# SensWear_Haptic.net
KiCad netlist of a schematic drawn in Altium Designer
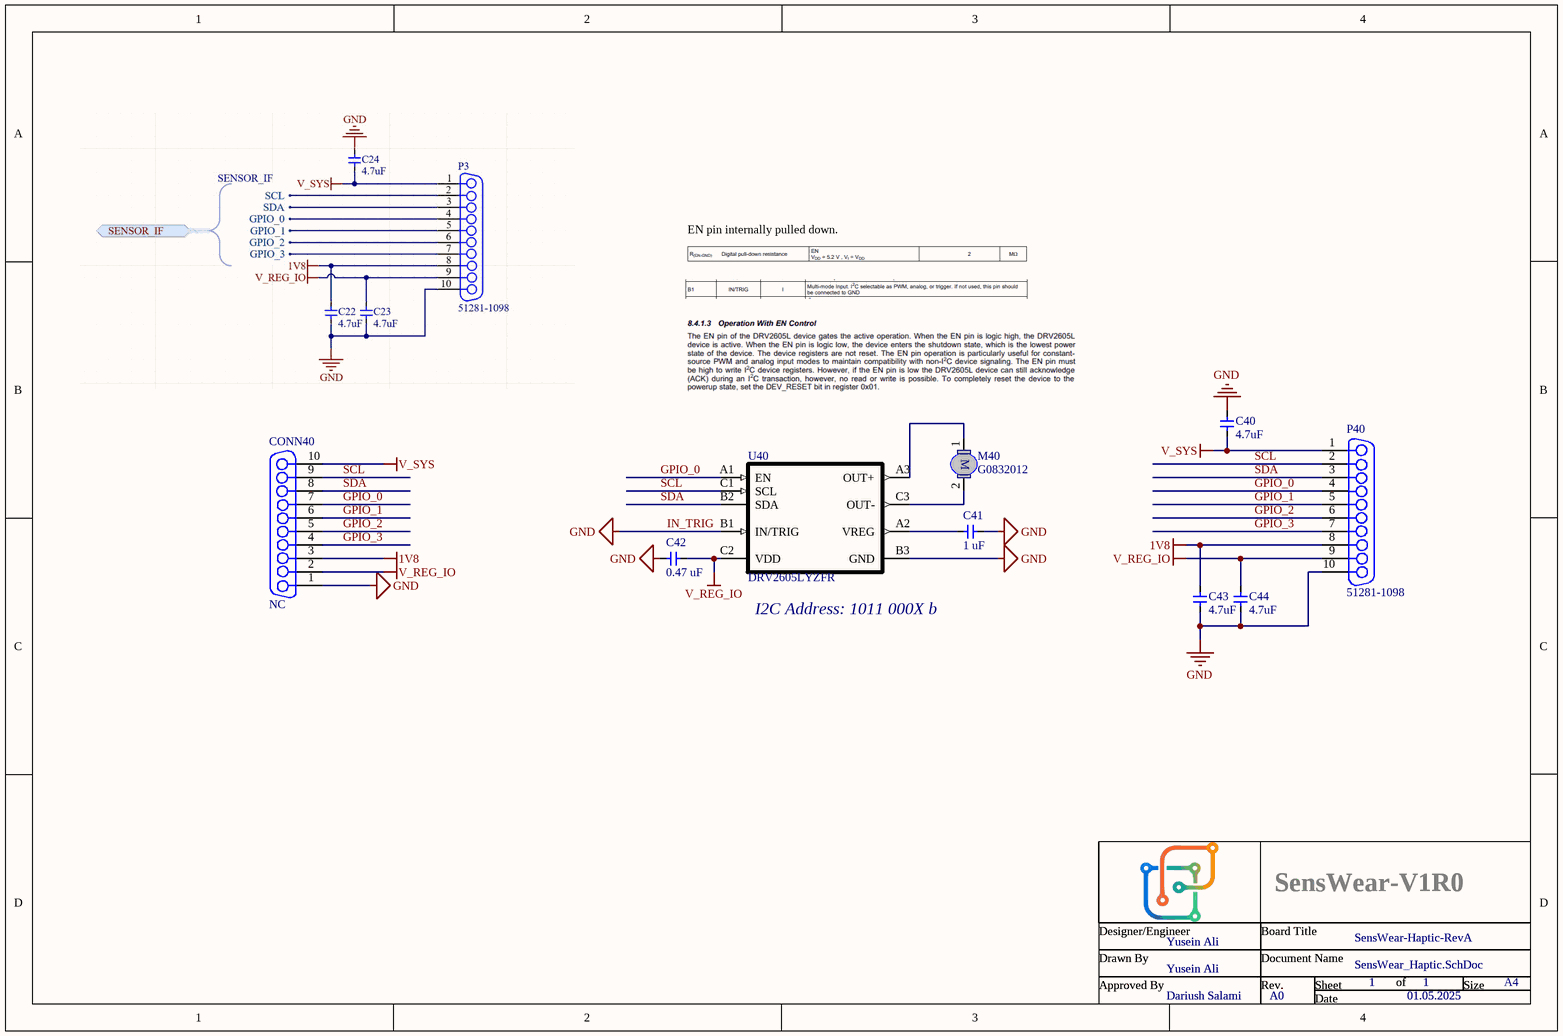
[diagram p0: SensWear_Haptic.SchDoc]

(export (version "E")
  (design (tool "Eeschema 10.0.6"))
  (components
    (comp (ref "C40")
      (value "4.7uF")
      (footprint "CAPC1005X05N")
      (description "Multilayer Ceramic Capacitor, 4.7 uF, 10 V, ± 20%, X5R, 0402 [1005 Metric]")
      (fields
        (field (name "MANUFACTURER") "Murata")
        (field (name "MANUFACTURER PART NUMBER") "GRM155R61A475MEAAD")
      )
      (libsource (lib "OpenRingComponents") (part "GRM155R61A475MEAAD"))
    )
    (comp (ref "C41")
      (value "1 uF")
      (footprint "CAPC1005X05N")
      (description "CAP CER 1UF 10V X5R 0402")
      (fields
        (field (name "MANUFACTURER") "Murata Electronics North America")
        (field (name "MANUFACTURER PART NUMBER") "GRM155R61A105KE15D")
      )
      (libsource (lib "OpenRingComponents") (part "GRM155R61A105KE15D"))
    )
    (comp (ref "C42")
      (value "0.47 uF")
      (footprint "CAPC1005X05N")
      (description "CAP CER 0.47UF 10V X5R 0402")
      (fields
        (field (name "MANUFACTURER") "Murata Electronics North America")
        (field (name "MANUFACTURER PART NUMBER") "GRM155R61A474KE15D")
      )
      (libsource (lib "OpenRingComponents") (part "GRM155R61A474KE15D"))
    )
    (comp (ref "C43")
      (value "4.7uF")
      (footprint "CAPC1005X05N")
      (description "Multilayer Ceramic Capacitor, 4.7 uF, 10 V, ± 20%, X5R, 0402 [1005 Metric]")
      (fields
        (field (name "MANUFACTURER") "Murata")
        (field (name "MANUFACTURER PART NUMBER") "GRM155R61A475MEAAD")
      )
      (libsource (lib "OpenRingComponents") (part "GRM155R61A475MEAAD"))
    )
    (comp (ref "C44")
      (value "4.7uF")
      (footprint "CAPC1005X05N")
      (description "Multilayer Ceramic Capacitor, 4.7 uF, 10 V, ± 20%, X5R, 0402 [1005 Metric]")
      (fields
        (field (name "MANUFACTURER") "Murata")
        (field (name "MANUFACTURER PART NUMBER") "GRM155R61A475MEAAD")
      )
      (libsource (lib "OpenRingComponents") (part "GRM155R61A475MEAAD"))
    )
    (comp (ref "CONN40")
      (value "NC")
      (footprint "51281-1098-PCB")
      (libsource (lib "Connectors") (part "51281-1098-PCB"))
    )
    (comp (ref "M40")
      (value "G0832012")
      (footprint "G0832012")
      (description "VIBRATION MOTOR 1.8V")
      (fields (field (name "MANUFACTURER") "Jinlong Machinery & Electronics, Inc."))
      (libsource (lib "OpenRingComponents") (part "G0832012"))
    )
    (comp (ref "P40")
      (value "51281-1098")
      (footprint "51281-1098")
      (description "FFC/FPC Connector, Surface Mount, Right-Angle, Non-ZIF, Dual Contact Style")
      (fields (field (name "MANUFACTURER") "Molex"))
      (libsource (lib "Connectors") (part "51281-1098"))
    )
    (comp (ref "U40")
      (value "DRV2605LYZFR")
      (footprint "BGA9C50P3X3_144X144X62")
      (fields (field (name "MANUFACTURER") "Texas Instruments"))
      (libsource (lib "OpenRingComponents") (part "DRV2605LYZFR"))
    )
  )
  (nets
    (net (code "1") (name "/GPIO_0") (class "Default")
      (node (ref "CONN40") (pin "7") (pinfunction "7_7") (pintype "passive"))
      (node (ref "P40") (pin "4") (pinfunction "4_4") (pintype "passive"))
      (node (ref "U40") (pin "A1") (pinfunction "EN_A1") (pintype "input"))
    )
    (net (code "2") (name "/GPIO_1") (class "Default")
      (node (ref "CONN40") (pin "6") (pinfunction "6_6") (pintype "passive"))
      (node (ref "P40") (pin "5") (pinfunction "5_5") (pintype "passive"))
    )
    (net (code "3") (name "/GPIO_2") (class "Default")
      (node (ref "CONN40") (pin "5") (pinfunction "5_5") (pintype "passive"))
      (node (ref "P40") (pin "6") (pinfunction "6_6") (pintype "passive"))
    )
    (net (code "4") (name "/GPIO_3") (class "Default")
      (node (ref "CONN40") (pin "4") (pinfunction "4_4") (pintype "passive"))
      (node (ref "P40") (pin "7") (pinfunction "7_7") (pintype "passive"))
    )
    (net (code "5") (name "/SCL") (class "Default")
      (node (ref "CONN40") (pin "9") (pinfunction "9_9") (pintype "passive"))
      (node (ref "P40") (pin "2") (pinfunction "2_2") (pintype "passive"))
      (node (ref "U40") (pin "C1") (pinfunction "SCL_C1") (pintype "input"))
    )
    (net (code "6") (name "/SDA") (class "Default")
      (node (ref "CONN40") (pin "8") (pinfunction "8_8") (pintype "passive"))
      (node (ref "P40") (pin "3") (pinfunction "3_3") (pintype "passive"))
      (node (ref "U40") (pin "B2") (pinfunction "SDA_B2") (pintype "passive"))
    )
    (net (code "7") (name "1V8") (class "Default")
      (node (ref "C43") (pin "2") (pinfunction "2_2") (pintype "passive"))
      (node (ref "CONN40") (pin "3") (pinfunction "3_3") (pintype "passive"))
      (node (ref "P40") (pin "8") (pinfunction "8_8") (pintype "passive"))
    )
    (net (code "8") (name "GND") (class "Default")
      (node (ref "C40") (pin "2") (pinfunction "2_2") (pintype "passive"))
      (node (ref "C41") (pin "1") (pinfunction "1_1") (pintype "passive"))
      (node (ref "C42") (pin "2") (pinfunction "2_2") (pintype "passive"))
      (node (ref "C43") (pin "1") (pinfunction "1_1") (pintype "passive"))
      (node (ref "C44") (pin "1") (pinfunction "1_1") (pintype "passive"))
      (node (ref "CONN40") (pin "1") (pinfunction "1_1") (pintype "passive"))
      (node (ref "P40") (pin "10") (pinfunction "10_10") (pintype "passive"))
      (node (ref "U40") (pin "B1") (pinfunction "IN/TRIG_B1") (pintype "input"))
      (node (ref "U40") (pin "B3") (pinfunction "GND_B3") (pintype "power_in"))
    )
    (net (code "9") (name "Net-(U40-OUT+)") (class "Default")
      (node (ref "M40") (pin "1") (pinfunction "V+_1") (pintype "passive"))
      (node (ref "U40") (pin "A3") (pinfunction "OUT+_A3") (pintype "output"))
    )
    (net (code "10") (name "Net-(U40-OUT-)") (class "Default")
      (node (ref "M40") (pin "2") (pinfunction "V+_2") (pintype "passive"))
      (node (ref "U40") (pin "C3") (pinfunction "OUT-_C3") (pintype "output"))
    )
    (net (code "11") (name "Net-(U40-VREG)") (class "Default")
      (node (ref "C41") (pin "2") (pinfunction "2_2") (pintype "passive"))
      (node (ref "U40") (pin "A2") (pinfunction "VREG_A2") (pintype "output"))
    )
    (net (code "12") (name "V_REG_IO") (class "Default")
      (node (ref "C42") (pin "1") (pinfunction "1_1") (pintype "passive"))
      (node (ref "C44") (pin "2") (pinfunction "2_2") (pintype "passive"))
      (node (ref "CONN40") (pin "2") (pinfunction "2_2") (pintype "passive"))
      (node (ref "P40") (pin "9") (pinfunction "9_9") (pintype "passive"))
      (node (ref "U40") (pin "C2") (pinfunction "VDD_C2") (pintype "power_in"))
    )
    (net (code "13") (name "V_SYS") (class "Default")
      (node (ref "C40") (pin "1") (pinfunction "1_1") (pintype "passive"))
      (node (ref "CONN40") (pin "10") (pinfunction "10_10") (pintype "passive"))
      (node (ref "P40") (pin "1") (pinfunction "1_1") (pintype "passive"))
    )
  )
)
